# main.net
KiCad netlist of a schematic drawn in EAGLE
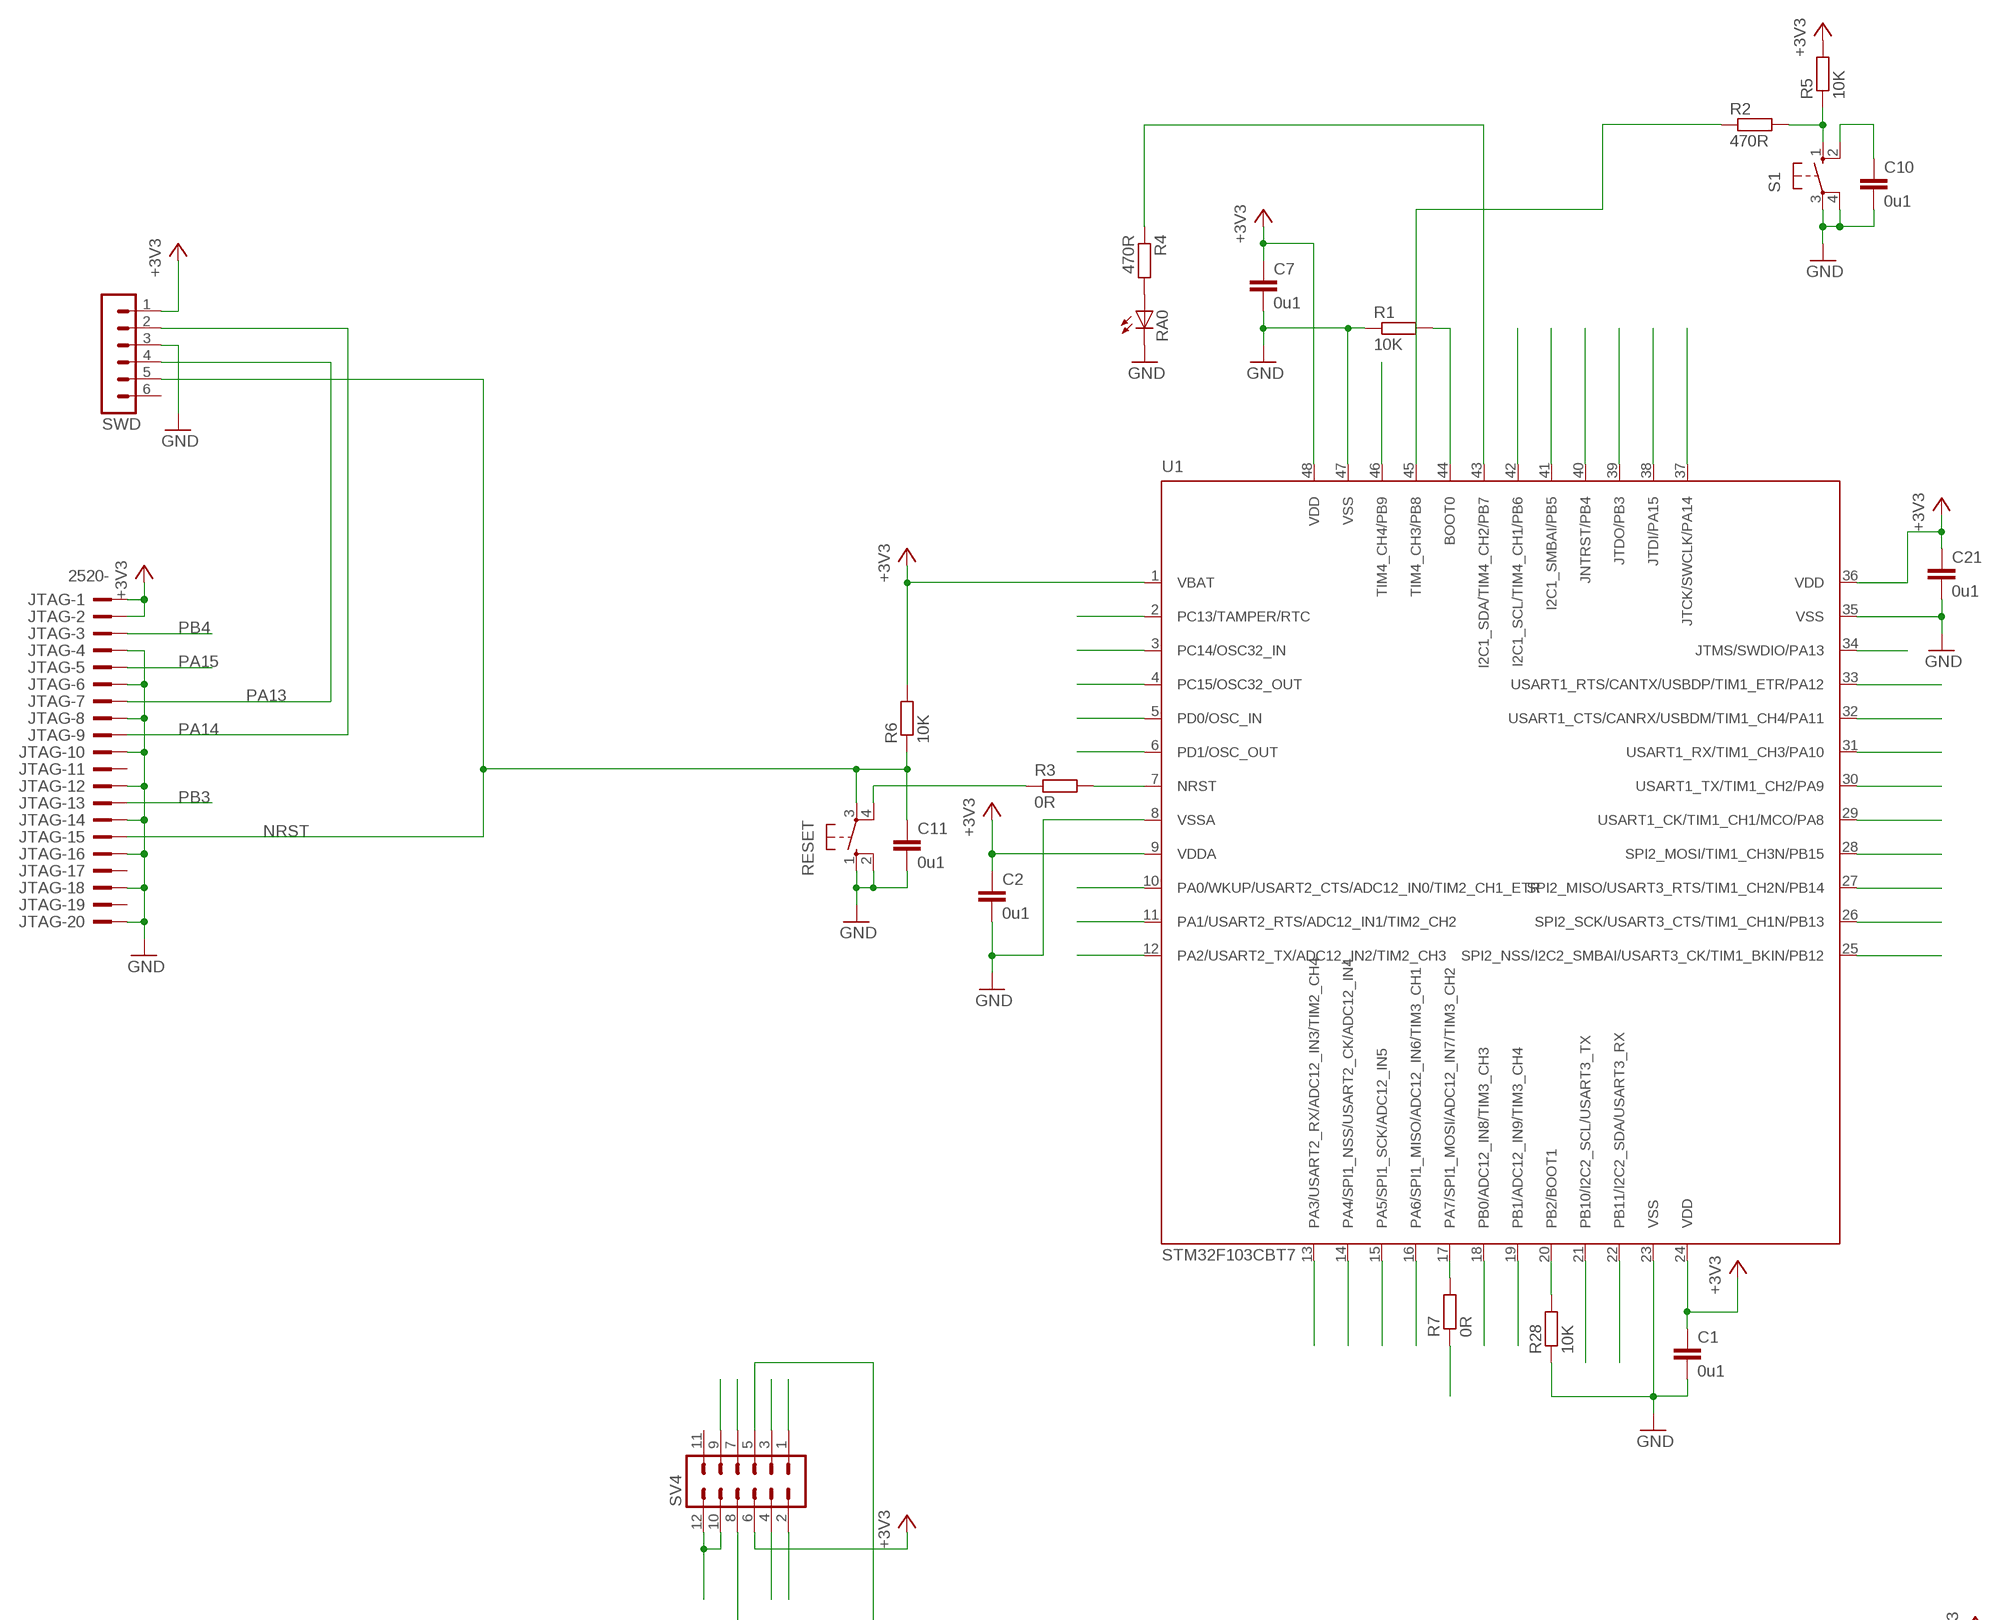
[diagram p0: schematic, sheet 1, part 1 of 2]
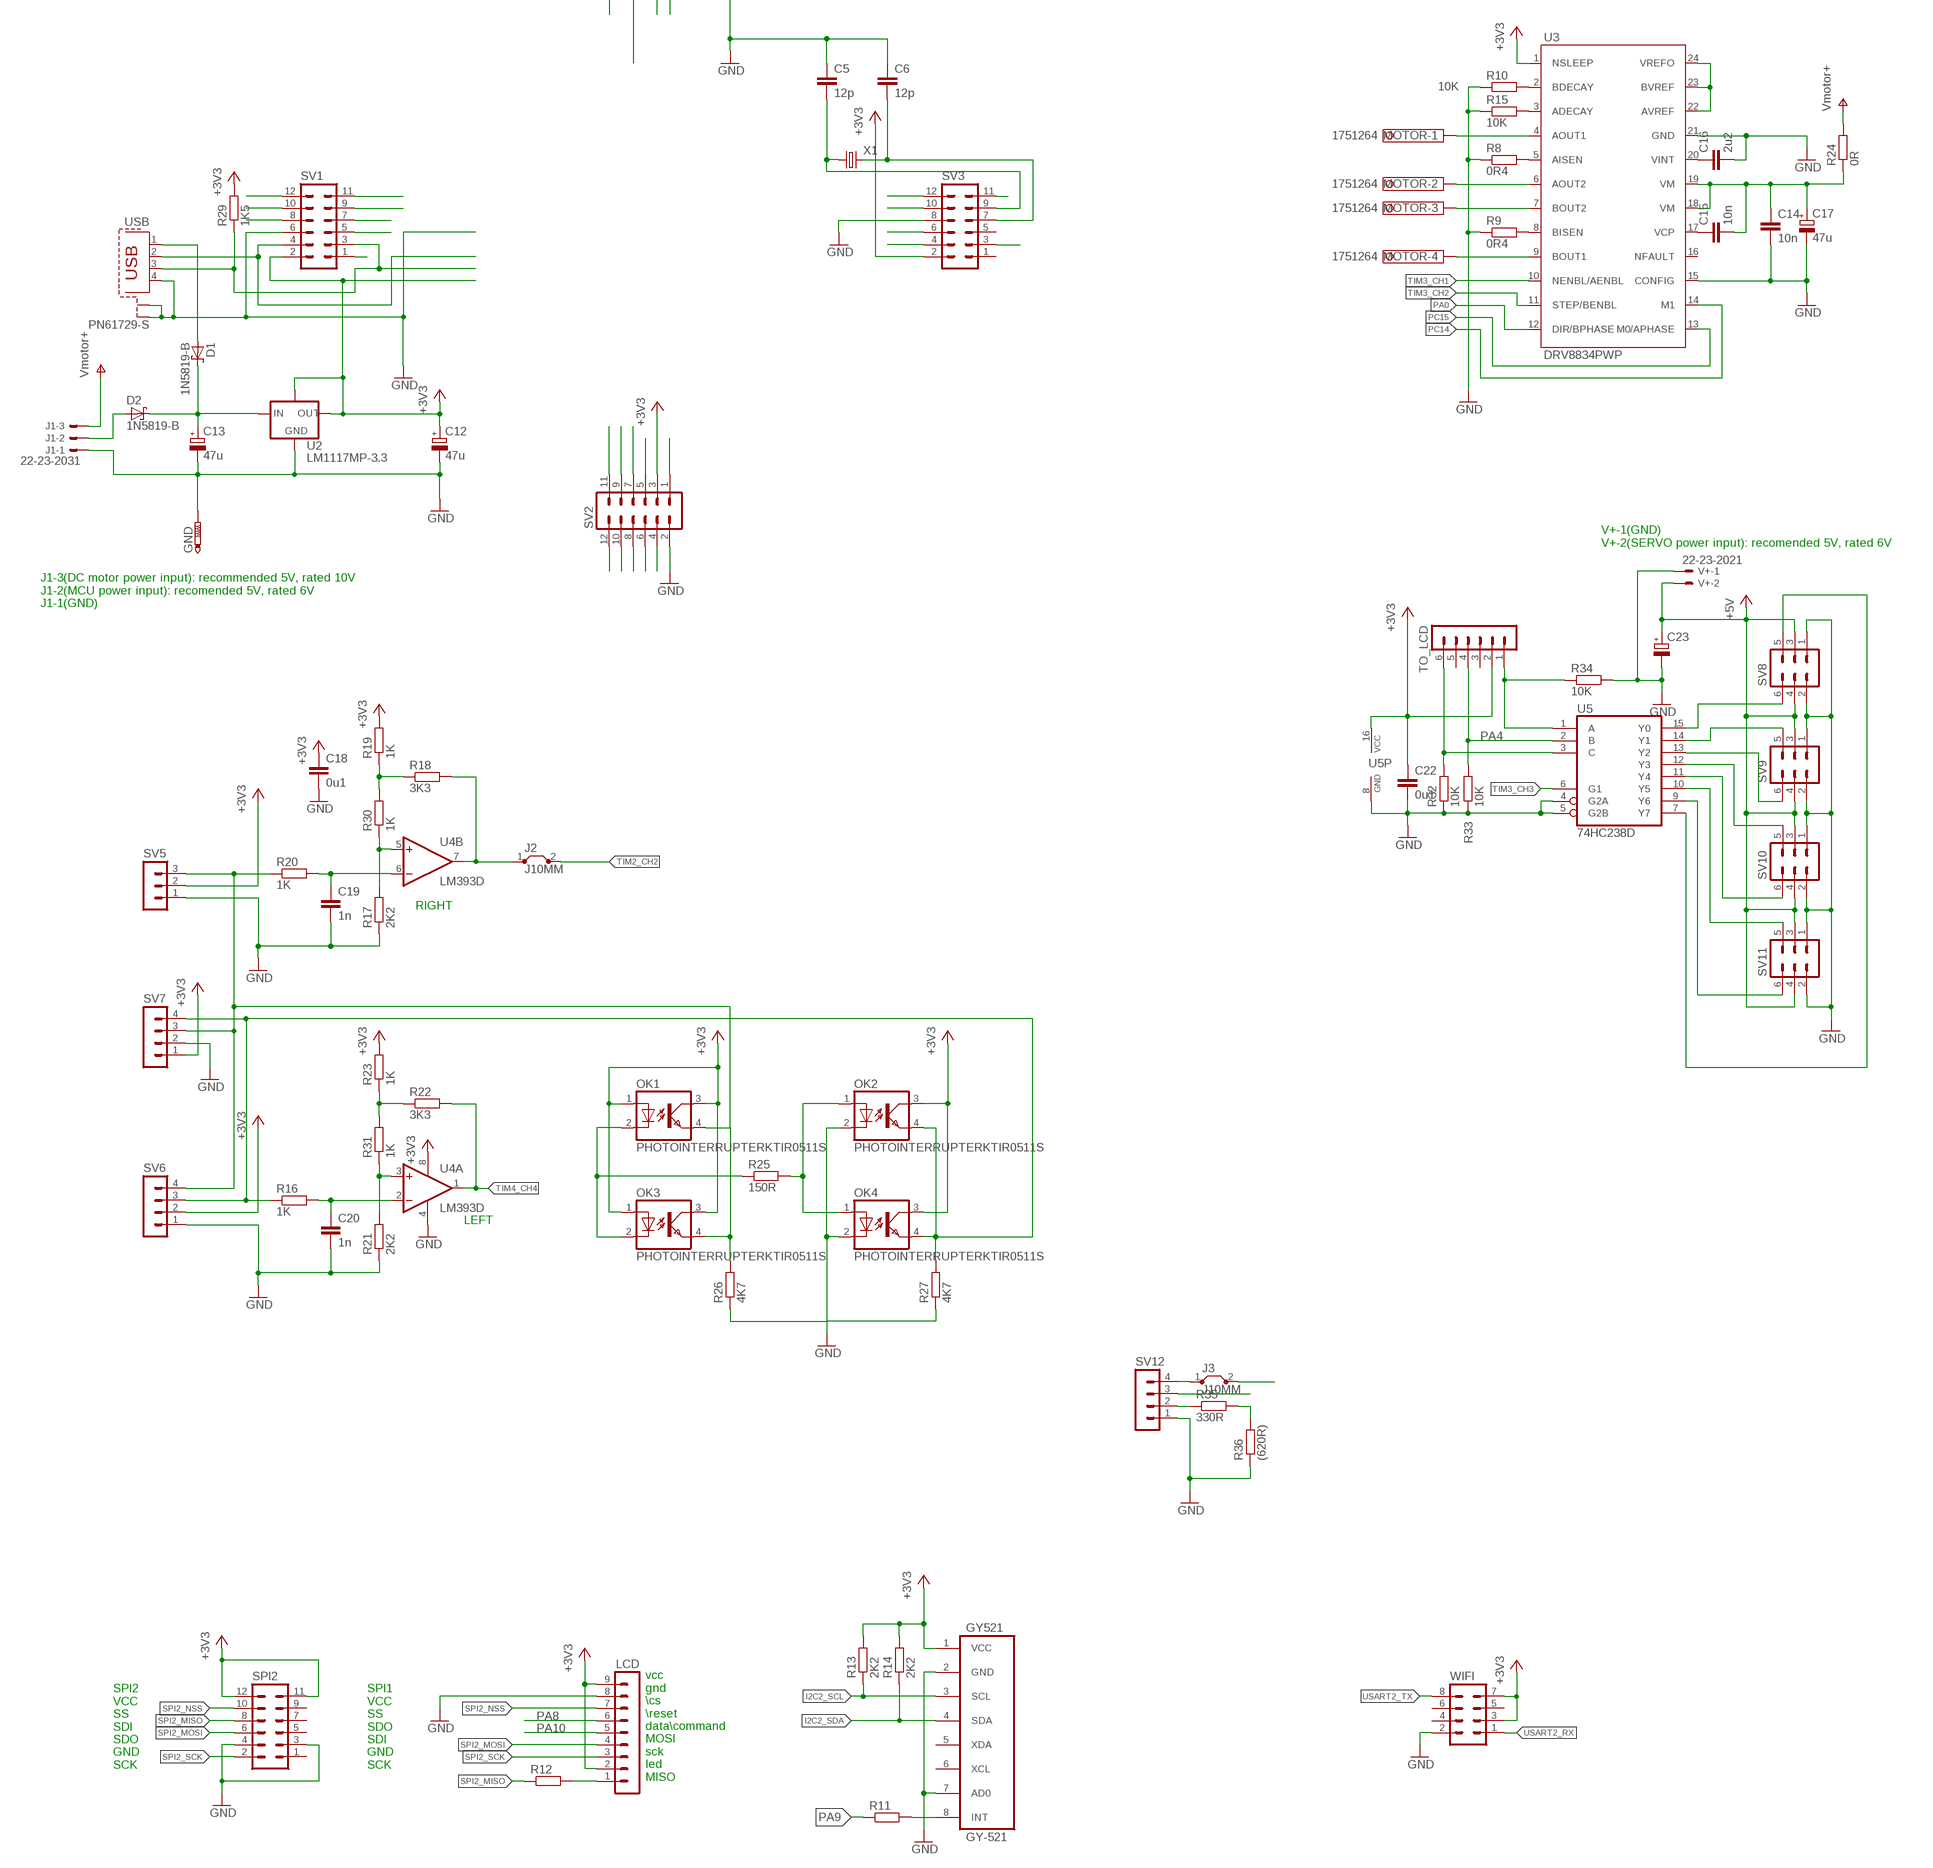
[diagram p1: schematic, sheet 1, part 2 of 2]

(export (version "E")
  (design (tool "Eeschema 10.0.6"))
  (components
    (comp (ref "C1")
      (value "0u1")
      (footprint "eagle-import:C0805")
      (libsource (lib "eagle-import") (part "C-EUC0805"))
    )
    (comp (ref "C2")
      (value "0u1")
      (footprint "eagle-import:C0805")
      (libsource (lib "eagle-import") (part "C-EUC0805"))
    )
    (comp (ref "C5")
      (value "12p")
      (footprint "eagle-import:C0805")
      (libsource (lib "eagle-import") (part "C-EUC0805"))
    )
    (comp (ref "C6")
      (value "12p")
      (footprint "eagle-import:C0805")
      (libsource (lib "eagle-import") (part "C-EUC0805"))
    )
    (comp (ref "C7")
      (value "0u1")
      (footprint "eagle-import:C0805")
      (libsource (lib "eagle-import") (part "C-EUC0805"))
    )
    (comp (ref "C10")
      (value "0u1")
      (footprint "eagle-import:C0805")
      (libsource (lib "eagle-import") (part "C-EUC0805"))
    )
    (comp (ref "C11")
      (value "0u1")
      (footprint "eagle-import:C0805")
      (libsource (lib "eagle-import") (part "C-EUC0805"))
    )
    (comp (ref "C12")
      (value "47u")
      (footprint "eagle-import:E1,8-4")
      (libsource (lib "eagle-import") (part "CPOL-EUE1.8-4"))
    )
    (comp (ref "C13")
      (value "47u")
      (footprint "eagle-import:E1,8-4")
      (libsource (lib "eagle-import") (part "CPOL-EUE1.8-4"))
    )
    (comp (ref "C14")
      (value "10n")
      (footprint "eagle-import:C0805")
      (libsource (lib "eagle-import") (part "C-EUC0805"))
    )
    (comp (ref "C15")
      (value "10n")
      (footprint "eagle-import:C0805")
      (libsource (lib "eagle-import") (part "C-EUC0805"))
    )
    (comp (ref "C16")
      (value "2u2")
      (footprint "eagle-import:C0805")
      (libsource (lib "eagle-import") (part "C-EUC0805"))
    )
    (comp (ref "C17")
      (value "47u")
      (footprint "eagle-import:E1,8-4")
      (libsource (lib "eagle-import") (part "CPOL-EUE1.8-4"))
    )
    (comp (ref "C18")
      (value "0u1")
      (footprint "eagle-import:C0805")
      (libsource (lib "eagle-import") (part "C-EUC0805"))
    )
    (comp (ref "C19")
      (value "1n")
      (footprint "eagle-import:C0805")
      (libsource (lib "eagle-import") (part "C-EUC0805"))
    )
    (comp (ref "C20")
      (value "1n")
      (footprint "eagle-import:C0805")
      (libsource (lib "eagle-import") (part "C-EUC0805"))
    )
    (comp (ref "C21")
      (value "0u1")
      (footprint "eagle-import:C0805")
      (libsource (lib "eagle-import") (part "C-EUC0805"))
    )
    (comp (ref "C22")
      (value "0u1")
      (footprint "eagle-import:C0805")
      (libsource (lib "eagle-import") (part "C-EUC0805"))
    )
    (comp (ref "C23")
      (value "CPOL-EUE2.5-7")
      (footprint "eagle-import:E2,5-7")
      (libsource (lib "eagle-import") (part "CPOL-EUE2.5-7"))
    )
    (comp (ref "D1")
      (value "1N5819-B")
      (footprint "eagle-import:DO41-7.6")
      (libsource (lib "eagle-import") (part "1N5819-B"))
    )
    (comp (ref "D2")
      (value "1N5819-B")
      (footprint "eagle-import:DO41-7.6")
      (libsource (lib "eagle-import") (part "1N5819-B"))
    )
    (comp (ref "GND")
      (value "PTR1PAD1-13")
      (footprint "eagle-import:P1-13")
      (libsource (lib "eagle-import") (part "PTR1PAD1-13"))
    )
    (comp (ref "GY521")
      (value "GY-521")
      (footprint "eagle-import:GY-521")
      (libsource (lib "eagle-import") (part "GY-521"))
    )
    (comp (ref "J1")
      (value "22-23-2031")
      (footprint "eagle-import:22-23-2031")
      (fields (field (name "MF") "MOLEX"))
      (libsource (lib "eagle-import") (part "22-23-2031"))
    )
    (comp (ref "J2")
      (value "J10MM")
      (footprint "eagle-import:10")
      (libsource (lib "eagle-import") (part "J10MM"))
    )
    (comp (ref "J3")
      (value "J10MM")
      (footprint "eagle-import:10")
      (libsource (lib "eagle-import") (part "J10MM"))
    )
    (comp (ref "JTAG")
      (value "2520-")
      (footprint "eagle-import:PAK100_2500-20")
      (libsource (lib "eagle-import") (part "2520-"))
    )
    (comp (ref "LCD")
      (value "MA09-1")
      (footprint "eagle-import:MA09-1")
      (libsource (lib "eagle-import") (part "MA09-1"))
    )
    (comp (ref "MOTOR")
      (value "1751264")
      (footprint "eagle-import:1751264")
      (libsource (lib "eagle-import") (part "1751264"))
    )
    (comp (ref "OK1")
      (value "PHOTOINTERRUPTERKTIR0511S")
      (footprint "eagle-import:KTIR0511S")
      (libsource (lib "eagle-import") (part "PHOTOINTERRUPTERKTIR0511S"))
    )
    (comp (ref "OK2")
      (value "PHOTOINTERRUPTERKTIR0511S")
      (footprint "eagle-import:KTIR0511S")
      (libsource (lib "eagle-import") (part "PHOTOINTERRUPTERKTIR0511S"))
    )
    (comp (ref "OK3")
      (value "PHOTOINTERRUPTERKTIR0511S")
      (footprint "eagle-import:KTIR0511S")
      (libsource (lib "eagle-import") (part "PHOTOINTERRUPTERKTIR0511S"))
    )
    (comp (ref "OK4")
      (value "PHOTOINTERRUPTERKTIR0511S")
      (footprint "eagle-import:KTIR0511S")
      (libsource (lib "eagle-import") (part "PHOTOINTERRUPTERKTIR0511S"))
    )
    (comp (ref "R1")
      (value "10K")
      (footprint "eagle-import:M0805")
      (libsource (lib "eagle-import") (part "R-EU_M0805"))
    )
    (comp (ref "R2")
      (value "470R")
      (footprint "eagle-import:0207_10")
      (libsource (lib "eagle-import") (part "R-EU_0207/10"))
    )
    (comp (ref "R3")
      (value "0R")
      (footprint "eagle-import:0207_10")
      (libsource (lib "eagle-import") (part "R-EU_0207/10"))
    )
    (comp (ref "R4")
      (value "470R")
      (footprint "eagle-import:0207_10")
      (libsource (lib "eagle-import") (part "R-EU_0207/10"))
    )
    (comp (ref "R5")
      (value "10K")
      (footprint "eagle-import:0207_10")
      (libsource (lib "eagle-import") (part "R-EU_0207/10"))
    )
    (comp (ref "R6")
      (value "10K")
      (footprint "eagle-import:M0805")
      (libsource (lib "eagle-import") (part "R-EU_M0805"))
    )
    (comp (ref "R7")
      (value "0R")
      (footprint "eagle-import:0207_10")
      (libsource (lib "eagle-import") (part "R-EU_0207/10"))
    )
    (comp (ref "R8")
      (value "0R4")
      (footprint "eagle-import:R2010")
      (libsource (lib "eagle-import") (part "R-EU_R2010"))
    )
    (comp (ref "R9")
      (value "0R4")
      (footprint "eagle-import:R2010")
      (libsource (lib "eagle-import") (part "R-EU_R2010"))
    )
    (comp (ref "R10")
      (value "10K")
      (footprint "eagle-import:R0805")
      (libsource (lib "eagle-import") (part "R-EU_R0805"))
    )
    (comp (ref "R11")
      (value "R-EU_0207/10")
      (footprint "eagle-import:0207_10")
      (libsource (lib "eagle-import") (part "R-EU_0207/10"))
    )
    (comp (ref "R12")
      (value "R-EU_0207/10")
      (footprint "eagle-import:0207_10")
      (libsource (lib "eagle-import") (part "R-EU_0207/10"))
    )
    (comp (ref "R13")
      (value "2K2")
      (footprint "eagle-import:M0805")
      (libsource (lib "eagle-import") (part "R-EU_M0805"))
    )
    (comp (ref "R14")
      (value "2K2")
      (footprint "eagle-import:M0805")
      (libsource (lib "eagle-import") (part "R-EU_M0805"))
    )
    (comp (ref "R15")
      (value "10K")
      (footprint "eagle-import:R0805")
      (libsource (lib "eagle-import") (part "R-EU_R0805"))
    )
    (comp (ref "R16")
      (value "1K")
      (footprint "eagle-import:0207_10")
      (libsource (lib "eagle-import") (part "R-EU_0207/10"))
    )
    (comp (ref "R17")
      (value "2K2")
      (footprint "eagle-import:M0805")
      (libsource (lib "eagle-import") (part "R-EU_M0805"))
    )
    (comp (ref "R18")
      (value "3K3")
      (footprint "eagle-import:M0805")
      (libsource (lib "eagle-import") (part "R-EU_M0805"))
    )
    (comp (ref "R19")
      (value "1K")
      (footprint "eagle-import:M0805")
      (libsource (lib "eagle-import") (part "R-EU_M0805"))
    )
    (comp (ref "R20")
      (value "1K")
      (footprint "eagle-import:0207_10")
      (libsource (lib "eagle-import") (part "R-EU_0207/10"))
    )
    (comp (ref "R21")
      (value "2K2")
      (footprint "eagle-import:M0805")
      (libsource (lib "eagle-import") (part "R-EU_M0805"))
    )
    (comp (ref "R22")
      (value "3K3")
      (footprint "eagle-import:M0805")
      (libsource (lib "eagle-import") (part "R-EU_M0805"))
    )
    (comp (ref "R23")
      (value "1K")
      (footprint "eagle-import:M0805")
      (libsource (lib "eagle-import") (part "R-EU_M0805"))
    )
    (comp (ref "R24")
      (value "0R")
      (footprint "eagle-import:0207_10")
      (libsource (lib "eagle-import") (part "R-EU_0207/10"))
    )
    (comp (ref "R25")
      (value "150R")
      (footprint "eagle-import:0207_10")
      (libsource (lib "eagle-import") (part "R-EU_0207/10"))
    )
    (comp (ref "R26")
      (value "4K7")
      (footprint "eagle-import:M0805")
      (libsource (lib "eagle-import") (part "R-EU_M0805"))
    )
    (comp (ref "R27")
      (value "4K7")
      (footprint "eagle-import:M0805")
      (libsource (lib "eagle-import") (part "R-EU_M0805"))
    )
    (comp (ref "R28")
      (value "10K")
      (footprint "eagle-import:M0805")
      (libsource (lib "eagle-import") (part "R-EU_M0805"))
    )
    (comp (ref "R29")
      (value "1K5")
      (footprint "eagle-import:M0805")
      (libsource (lib "eagle-import") (part "R-EU_M0805"))
    )
    (comp (ref "R30")
      (value "1K")
      (footprint "eagle-import:M0805")
      (libsource (lib "eagle-import") (part "R-EU_M0805"))
    )
    (comp (ref "R31")
      (value "1K")
      (footprint "eagle-import:M0805")
      (libsource (lib "eagle-import") (part "R-EU_M0805"))
    )
    (comp (ref "R32")
      (value "10K")
      (footprint "eagle-import:M0805")
      (libsource (lib "eagle-import") (part "R-EU_M0805"))
    )
    (comp (ref "R33")
      (value "10K")
      (footprint "eagle-import:M0805")
      (libsource (lib "eagle-import") (part "R-EU_M0805"))
    )
    (comp (ref "R34")
      (value "10K")
      (footprint "eagle-import:M0805")
      (libsource (lib "eagle-import") (part "R-EU_M0805"))
    )
    (comp (ref "R35")
      (value "330R")
      (footprint "eagle-import:M0805")
      (libsource (lib "eagle-import") (part "R-EU_M0805"))
    )
    (comp (ref "R36")
      (value "(620R)")
      (footprint "eagle-import:M0805")
      (libsource (lib "eagle-import") (part "R-EU_M0805"))
    )
    (comp (ref "RA0")
      (value "LED3MM")
      (footprint "eagle-import:LED3MM")
      (libsource (lib "eagle-import") (part "LED3MM"))
    )
    (comp (ref "RESET")
      (value "10-XX")
      (footprint "eagle-import:B3F-10XX")
      (fields (field (name "MPN") "B3F-1000"))
      (libsource (lib "eagle-import") (part "10-XX"))
    )
    (comp (ref "S1")
      (value "10-XX")
      (footprint "eagle-import:B3F-10XX")
      (fields (field (name "MPN") "B3F-1000"))
      (libsource (lib "eagle-import") (part "10-XX"))
    )
    (comp (ref "SPI2")
      (value "MA06-2")
      (footprint "eagle-import:MA06-2")
      (libsource (lib "eagle-import") (part "MA06-2"))
    )
    (comp (ref "SV1")
      (value "MA06-2")
      (footprint "eagle-import:MA06-2")
      (libsource (lib "eagle-import") (part "MA06-2"))
    )
    (comp (ref "SV2")
      (value "MA06-2")
      (footprint "eagle-import:MA06-2")
      (libsource (lib "eagle-import") (part "MA06-2"))
    )
    (comp (ref "SV3")
      (value "MA06-2")
      (footprint "eagle-import:MA06-2")
      (libsource (lib "eagle-import") (part "MA06-2"))
    )
    (comp (ref "SV4")
      (value "MA06-2")
      (footprint "eagle-import:MA06-2")
      (libsource (lib "eagle-import") (part "MA06-2"))
    )
    (comp (ref "SV5")
      (value "MA03-1")
      (footprint "eagle-import:MA03-1")
      (libsource (lib "eagle-import") (part "MA03-1"))
    )
    (comp (ref "SV6")
      (value "MA04-1")
      (footprint "eagle-import:MA04-1")
      (libsource (lib "eagle-import") (part "MA04-1"))
    )
    (comp (ref "SV7")
      (value "MA04-1")
      (footprint "eagle-import:MA04-1")
      (libsource (lib "eagle-import") (part "MA04-1"))
    )
    (comp (ref "SV8")
      (value "MA03-2")
      (footprint "eagle-import:MA03-2")
      (libsource (lib "eagle-import") (part "MA03-2"))
    )
    (comp (ref "SV9")
      (value "MA03-2")
      (footprint "eagle-import:MA03-2")
      (libsource (lib "eagle-import") (part "MA03-2"))
    )
    (comp (ref "SV10")
      (value "MA03-2")
      (footprint "eagle-import:MA03-2")
      (libsource (lib "eagle-import") (part "MA03-2"))
    )
    (comp (ref "SV11")
      (value "MA03-2")
      (footprint "eagle-import:MA03-2")
      (libsource (lib "eagle-import") (part "MA03-2"))
    )
    (comp (ref "SV12")
      (value "MA04-1")
      (footprint "eagle-import:MA04-1")
      (libsource (lib "eagle-import") (part "MA04-1"))
    )
    (comp (ref "SWD")
      (value "MA06-1")
      (footprint "eagle-import:MA06-1")
      (libsource (lib "eagle-import") (part "MA06-1"))
    )
    (comp (ref "TO_LCD")
      (value "MA06-1")
      (footprint "eagle-import:MA06-1")
      (libsource (lib "eagle-import") (part "MA06-1"))
    )
    (comp (ref "U1")
      (value "STM32F103CBT7")
      (footprint "eagle-import:LQFP48-7X7")
      (libsource (lib "eagle-import") (part "STM32F103CBT7"))
    )
    (comp (ref "U2")
      (value "LM1117MP-3.3")
      (footprint "eagle-import:SOT230P700X180-4N")
      (libsource (lib "eagle-import") (part "LM1117"))
    )
    (comp (ref "U3")
      (value "DRV8834PWP")
      (footprint "eagle-import:PWP-TSSOP24")
      (libsource (lib "eagle-import") (part "DRV8834PWP"))
    )
    (comp (ref "U4")
      (value "LM393D")
      (footprint "eagle-import:SO08")
      (libsource (lib "eagle-import") (part "LM393D"))
    )
    (comp (ref "U5")
      (value "74HC238D")
      (footprint "eagle-import:SO16")
      (libsource (lib "eagle-import") (part "74238DHC"))
    )
    (comp (ref "USB")
      (value "PN61729-S")
      (footprint "eagle-import:PN61729-S")
      (libsource (lib "eagle-import") (part "PN61729-S"))
    )
    (comp (ref "V+")
      (value "22-23-2021")
      (footprint "eagle-import:22-23-2021")
      (fields (field (name "MF") "MOLEX"))
      (libsource (lib "eagle-import") (part "22-23-2021"))
    )
    (comp (ref "WIFI")
      (value "MA04-2")
      (footprint "eagle-import:MA04-2")
      (libsource (lib "eagle-import") (part "MA04-2"))
    )
    (comp (ref "X1")
      (value "CRYSTALHC49S")
      (footprint "eagle-import:HC49_S")
      (libsource (lib "eagle-import") (part "CRYSTALHC49S"))
    )
  )
  (nets
    (net (code "1") (name "+3V3") (class "Default")
      (node (ref "C1") (pin "1") (pinfunction "1_1") (pintype "passive"))
      (node (ref "C12") (pin "+") (pinfunction "+_+") (pintype "passive"))
      (node (ref "C18") (pin "1") (pinfunction "1_1") (pintype "passive"))
      (node (ref "C2") (pin "1") (pinfunction "1_1") (pintype "passive"))
      (node (ref "C21") (pin "1") (pinfunction "1_1") (pintype "passive"))
      (node (ref "C22") (pin "1") (pinfunction "1_1") (pintype "passive"))
      (node (ref "C7") (pin "1") (pinfunction "1_1") (pintype "passive"))
      (node (ref "GY521") (pin "1") (pinfunction "VCC_1") (pintype "power_in"))
      (node (ref "JTAG") (pin "1") (pinfunction "KL_1") (pintype "passive"))
      (node (ref "JTAG") (pin "2") (pinfunction "KL_2") (pintype "passive"))
      (node (ref "LCD") (pin "2") (pinfunction "2_2") (pintype "passive"))
      (node (ref "LCD") (pin "9") (pinfunction "9_9") (pintype "passive"))
      (node (ref "OK1") (pin "1") (pinfunction "A_1") (pintype "passive"))
      (node (ref "OK1") (pin "3") (pinfunction "COL_3") (pintype "passive"))
      (node (ref "OK2") (pin "3") (pinfunction "COL_3") (pintype "passive"))
      (node (ref "OK3") (pin "1") (pinfunction "A_1") (pintype "passive"))
      (node (ref "OK3") (pin "3") (pinfunction "COL_3") (pintype "passive"))
      (node (ref "OK4") (pin "3") (pinfunction "COL_3") (pintype "passive"))
      (node (ref "R13") (pin "2") (pinfunction "2_2") (pintype "passive"))
      (node (ref "R14") (pin "2") (pinfunction "2_2") (pintype "passive"))
      (node (ref "R19") (pin "2") (pinfunction "2_2") (pintype "passive"))
      (node (ref "R23") (pin "2") (pinfunction "2_2") (pintype "passive"))
      (node (ref "R29") (pin "2") (pinfunction "2_2") (pintype "passive"))
      (node (ref "R5") (pin "2") (pinfunction "2_2") (pintype "passive"))
      (node (ref "R6") (pin "2") (pinfunction "2_2") (pintype "passive"))
      (node (ref "SPI2") (pin "11") (pinfunction "11_11") (pintype "passive"))
      (node (ref "SPI2") (pin "12") (pinfunction "12_12") (pintype "passive"))
      (node (ref "SV1") (pin "2") (pinfunction "2_2") (pintype "passive"))
      (node (ref "SV2") (pin "3") (pinfunction "3_3") (pintype "passive"))
      (node (ref "SV3") (pin "2") (pinfunction "2_2") (pintype "passive"))
      (node (ref "SV4") (pin "6") (pinfunction "6_6") (pintype "passive"))
      (node (ref "SV5") (pin "2") (pinfunction "2_2") (pintype "passive"))
      (node (ref "SV6") (pin "2") (pinfunction "2_2") (pintype "passive"))
      (node (ref "SV7") (pin "1") (pinfunction "1_1") (pintype "passive"))
      (node (ref "SWD") (pin "1") (pinfunction "1_1") (pintype "passive"))
      (node (ref "TO_LCD") (pin "2") (pinfunction "2_2") (pintype "passive"))
      (node (ref "U1") (pin "1") (pinfunction "VBAT_1") (pintype "input"))
      (node (ref "U1") (pin "24") (pinfunction "VDD_24") (pintype "power_in"))
      (node (ref "U1") (pin "36") (pinfunction "VDD_36") (pintype "power_in"))
      (node (ref "U1") (pin "48") (pinfunction "VDD_48") (pintype "power_in"))
      (node (ref "U1") (pin "9") (pinfunction "VDDA_9") (pintype "power_in"))
      (node (ref "U2") (pin "2") (pinfunction "OUT_2") (pintype "passive"))
      (node (ref "U2") (pin "4") (pinfunction "TAB_4") (pintype "passive"))
      (node (ref "U3") (pin "1") (pinfunction "NSLEEP_1") (pintype "passive"))
      (node (ref "U4") (pin "8") (pinfunction "V+_8") (pintype "power_in"))
      (node (ref "U5") (pin "16") (pinfunction "VCC_16") (pintype "power_in"))
      (node (ref "WIFI") (pin "3") (pinfunction "3_3") (pintype "passive"))
      (node (ref "WIFI") (pin "7") (pinfunction "7_7") (pintype "passive"))
    )
    (net (code "2") (name "+5V") (class "Default")
      (node (ref "C23") (pin "+") (pinfunction "+_+") (pintype "passive"))
      (node (ref "SV10") (pin "3") (pinfunction "3_3") (pintype "passive"))
      (node (ref "SV10") (pin "4") (pinfunction "4_4") (pintype "passive"))
      (node (ref "SV11") (pin "3") (pinfunction "3_3") (pintype "passive"))
      (node (ref "SV11") (pin "4") (pinfunction "4_4") (pintype "passive"))
      (node (ref "SV8") (pin "3") (pinfunction "3_3") (pintype "passive"))
      (node (ref "SV8") (pin "4") (pinfunction "4_4") (pintype "passive"))
      (node (ref "SV9") (pin "3") (pinfunction "3_3") (pintype "passive"))
      (node (ref "SV9") (pin "4") (pinfunction "4_4") (pintype "passive"))
      (node (ref "V+") (pin "2") (pinfunction "S_2") (pintype "passive"))
    )
    (net (code "3") (name "/BOOT0") (class "Default")
      (node (ref "R1") (pin "2") (pinfunction "2_2") (pintype "passive"))
      (node (ref "SV2") (pin "5") (pinfunction "5_5") (pintype "passive"))
      (node (ref "U1") (pin "44") (pinfunction "BOOT0_44") (pintype "input"))
    )
    (net (code "4") (name "/BOOT1") (class "Default")
      (node (ref "R28") (pin "2") (pinfunction "2_2") (pintype "passive"))
      (node (ref "SV4") (pin "8") (pinfunction "8_8") (pintype "passive"))
      (node (ref "U1") (pin "20") (pinfunction "PB2/BOOT1_20") (pintype "bidirectional"))
    )
    (net (code "5") (name "/N$13") (class "Default")
      (node (ref "D2") (pin "A") (pinfunction "A_A") (pintype "passive"))
      (node (ref "J1") (pin "2") (pinfunction "S_2") (pintype "passive"))
      (node (ref "J3") (pin "2") (pinfunction "2_2") (pintype "passive"))
    )
    (net (code "6") (name "/NRST") (class "Default")
      (node (ref "C11") (pin "1") (pinfunction "1_1") (pintype "passive"))
      (node (ref "JTAG") (pin "15") (pinfunction "KL_15") (pintype "passive"))
      (node (ref "R6") (pin "1") (pinfunction "1_1") (pintype "passive"))
      (node (ref "RESET") (pin "3") (pinfunction "P_3") (pintype "passive"))
      (node (ref "SWD") (pin "5") (pinfunction "5_5") (pintype "passive"))
    )
    (net (code "7") (name "/PA4") (class "Default")
      (node (ref "R33") (pin "2") (pinfunction "2_2") (pintype "passive"))
      (node (ref "SV4") (pin "1") (pinfunction "1_1") (pintype "passive"))
      (node (ref "TO_LCD") (pin "4") (pinfunction "4_4") (pintype "passive"))
      (node (ref "U1") (pin "14") (pinfunction "PA4/SPI1_NSS/USART2_CK/ADC12_IN4_14") (pintype "bidirectional"))
      (node (ref "U5") (pin "2") (pinfunction "B_2") (pintype "input"))
    )
    (net (code "8") (name "/PA5") (class "Default")
      (node (ref "SV4") (pin "2") (pinfunction "2_2") (pintype "passive"))
      (node (ref "U1") (pin "15") (pinfunction "PA5/SPI1_SCK/ADC12_IN5_15") (pintype "bidirectional"))
    )
    (net (code "9") (name "/PA8") (class "Default")
      (node (ref "LCD") (pin "6") (pinfunction "6_6") (pintype "passive"))
      (node (ref "SV1") (pin "7") (pinfunction "7_7") (pintype "passive"))
      (node (ref "U1") (pin "29") (pinfunction "USART1_CK/TIM1_CH1/MCO/PA8_29") (pintype "bidirectional"))
    )
    (net (code "10") (name "/PA10") (class "Default")
      (node (ref "LCD") (pin "5") (pinfunction "5_5") (pintype "passive"))
      (node (ref "SV1") (pin "5") (pinfunction "5_5") (pintype "passive"))
      (node (ref "U1") (pin "31") (pinfunction "USART1_RX/TIM1_CH3/PA10_31") (pintype "bidirectional"))
    )
    (net (code "11") (name "/PA13") (class "Default")
      (node (ref "JTAG") (pin "7") (pinfunction "KL_7") (pintype "passive"))
      (node (ref "SV1") (pin "1") (pinfunction "1_1") (pintype "passive"))
      (node (ref "SWD") (pin "4") (pinfunction "4_4") (pintype "passive"))
      (node (ref "U1") (pin "34") (pinfunction "JTMS/SWDIO/PA13_34") (pintype "bidirectional"))
    )
    (net (code "12") (name "/PA14") (class "Default")
      (node (ref "JTAG") (pin "9") (pinfunction "KL_9") (pintype "passive"))
      (node (ref "SV2") (pin "12") (pinfunction "12_12") (pintype "passive"))
      (node (ref "SWD") (pin "2") (pinfunction "2_2") (pintype "passive"))
      (node (ref "U1") (pin "37") (pinfunction "JTCK/SWCLK/PA14_37") (pintype "bidirectional"))
    )
    (net (code "13") (name "/PA15") (class "Default")
      (node (ref "JTAG") (pin "5") (pinfunction "KL_5") (pintype "passive"))
      (node (ref "SV2") (pin "11") (pinfunction "11_11") (pintype "passive"))
      (node (ref "U1") (pin "38") (pinfunction "JTDI/PA15_38") (pintype "bidirectional"))
    )
    (net (code "14") (name "/PB1") (class "Default")
      (node (ref "SV4") (pin "7") (pinfunction "7_7") (pintype "passive"))
      (node (ref "U1") (pin "19") (pinfunction "PB1/ADC12_IN9/TIM3_CH4_19") (pintype "bidirectional"))
    )
    (net (code "15") (name "/PB3") (class "Default")
      (node (ref "JTAG") (pin "13") (pinfunction "KL_13") (pintype "passive"))
      (node (ref "SV2") (pin "10") (pinfunction "10_10") (pintype "passive"))
      (node (ref "U1") (pin "39") (pinfunction "JTDO/PB3_39") (pintype "bidirectional"))
    )
    (net (code "16") (name "/PB4") (class "Default")
      (node (ref "JTAG") (pin "3") (pinfunction "KL_3") (pintype "passive"))
      (node (ref "R35") (pin "2") (pinfunction "2_2") (pintype "passive"))
      (node (ref "R36") (pin "2") (pinfunction "2_2") (pintype "passive"))
      (node (ref "SV2") (pin "9") (pinfunction "9_9") (pintype "passive"))
      (node (ref "U1") (pin "40") (pinfunction "JNTRST/PB4_40") (pintype "bidirectional"))
    )
    (net (code "17") (name "/PB5") (class "Default")
      (node (ref "SV12") (pin "3") (pinfunction "3_3") (pintype "passive"))
      (node (ref "SV2") (pin "8") (pinfunction "8_8") (pintype "passive"))
      (node (ref "U1") (pin "41") (pinfunction "I2C1_SMBAI/PB5_41") (pintype "bidirectional"))
    )
    (net (code "18") (name "/PB6") (class "Default")
      (node (ref "SV2") (pin "7") (pinfunction "7_7") (pintype "passive"))
      (node (ref "U1") (pin "42") (pinfunction "I2C1_SCL/TIM4_CH1/PB6_42") (pintype "bidirectional"))
    )
    (net (code "19") (name "/PB7") (class "Default")
      (node (ref "R4") (pin "1") (pinfunction "1_1") (pintype "passive"))
      (node (ref "SV2") (pin "6") (pinfunction "6_6") (pintype "passive"))
      (node (ref "U1") (pin "43") (pinfunction "I2C1_SDA/TIM4_CH2/PB7_43") (pintype "bidirectional"))
    )
    (net (code "20") (name "/PB8") (class "Default")
      (node (ref "R2") (pin "1") (pinfunction "1_1") (pintype "passive"))
      (node (ref "SV2") (pin "4") (pinfunction "4_4") (pintype "passive"))
      (node (ref "U1") (pin "45") (pinfunction "TIM4_CH3/PB8_45") (pintype "bidirectional"))
    )
    (net (code "21") (name "/PC13") (class "Default")
      (node (ref "SV3") (pin "4") (pinfunction "4_4") (pintype "passive"))
      (node (ref "U1") (pin "2") (pinfunction "PC13/TAMPER/RTC_2") (pintype "bidirectional"))
    )
    (net (code "22") (name "/PD0") (class "Default")
      (node (ref "C6") (pin "2") (pinfunction "2_2") (pintype "passive"))
      (node (ref "SV3") (pin "7") (pinfunction "7_7") (pintype "passive"))
      (node (ref "U1") (pin "5") (pinfunction "PD0/OSC_IN_5") (pintype "bidirectional"))
      (node (ref "X1") (pin "2") (pinfunction "2_2") (pintype "passive"))
    )
    (net (code "23") (name "/PD1") (class "Default")
      (node (ref "C5") (pin "2") (pinfunction "2_2") (pintype "passive"))
      (node (ref "SV3") (pin "9") (pinfunction "9_9") (pintype "passive"))
      (node (ref "U1") (pin "6") (pinfunction "PD1/OSC_OUT_6") (pintype "bidirectional"))
      (node (ref "X1") (pin "1") (pinfunction "1_1") (pintype "passive"))
    )
    (net (code "24") (name "/USBDM") (class "Default")
      (node (ref "SV1") (pin "4") (pinfunction "4_4") (pintype "passive"))
      (node (ref "U1") (pin "32") (pinfunction "USART1_CTS/CANRX/USBDM/TIM1_CH4/PA11_32") (pintype "bidirectional"))
      (node (ref "USB") (pin "2") (pinfunction "2_2") (pintype "passive"))
    )
    (net (code "25") (name "/USBDP") (class "Default")
      (node (ref "R29") (pin "1") (pinfunction "1_1") (pintype "passive"))
      (node (ref "SV1") (pin "3") (pinfunction "3_3") (pintype "passive"))
      (node (ref "U1") (pin "33") (pinfunction "USART1_RTS/CANTX/USBDP/TIM1_ETR/PA12_33") (pintype "bidirectional"))
      (node (ref "USB") (pin "3") (pinfunction "3_3") (pintype "passive"))
    )
    (net (code "26") (name "GND") (class "Default")
      (node (ref "C1") (pin "2") (pinfunction "2_2") (pintype "passive"))
      (node (ref "C10") (pin "2") (pinfunction "2_2") (pintype "passive"))
      (node (ref "C11") (pin "2") (pinfunction "2_2") (pintype "passive"))
      (node (ref "C12") (pin "-") (pinfunction "-_-") (pintype "passive"))
      (node (ref "C13") (pin "-") (pinfunction "-_-") (pintype "passive"))
      (node (ref "C14") (pin "2") (pinfunction "2_2") (pintype "passive"))
      (node (ref "C16") (pin "2") (pinfunction "2_2") (pintype "passive"))
      (node (ref "C17") (pin "-") (pinfunction "-_-") (pintype "passive"))
      (node (ref "C18") (pin "2") (pinfunction "2_2") (pintype "passive"))
      (node (ref "C19") (pin "2") (pinfunction "2_2") (pintype "passive"))
      (node (ref "C2") (pin "2") (pinfunction "2_2") (pintype "passive"))
      (node (ref "C20") (pin "2") (pinfunction "2_2") (pintype "passive"))
      (node (ref "C21") (pin "2") (pinfunction "2_2") (pintype "passive"))
      (node (ref "C22") (pin "2") (pinfunction "2_2") (pintype "passive"))
      (node (ref "C23") (pin "-") (pinfunction "-_-") (pintype "passive"))
      (node (ref "C5") (pin "1") (pinfunction "1_1") (pintype "passive"))
      (node (ref "C6") (pin "1") (pinfunction "1_1") (pintype "passive"))
      (node (ref "C7") (pin "2") (pinfunction "2_2") (pintype "passive"))
      (node (ref "GND") (pin "TP") (pinfunction "TP_TP") (pintype "input"))
      (node (ref "GY521") (pin "2") (pinfunction "GND_2") (pintype "power_in"))
      (node (ref "GY521") (pin "7") (pinfunction "AD0_7") (pintype "input"))
      (node (ref "J1") (pin "1") (pinfunction "S_1") (pintype "passive"))
      (node (ref "JTAG") (pin "10") (pinfunction "KL_10") (pintype "passive"))
      (node (ref "JTAG") (pin "12") (pinfunction "KL_12") (pintype "passive"))
      (node (ref "JTAG") (pin "14") (pinfunction "KL_14") (pintype "passive"))
      (node (ref "JTAG") (pin "16") (pinfunction "KL_16") (pintype "passive"))
      (node (ref "JTAG") (pin "18") (pinfunction "KL_18") (pintype "passive"))
      (node (ref "JTAG") (pin "20") (pinfunction "KL_20") (pintype "passive"))
      (node (ref "JTAG") (pin "4") (pinfunction "KL_4") (pintype "passive"))
      (node (ref "JTAG") (pin "6") (pinfunction "KL_6") (pintype "passive"))
      (node (ref "JTAG") (pin "8") (pinfunction "KL_8") (pintype "passive"))
      (node (ref "LCD") (pin "8") (pinfunction "8_8") (pintype "passive"))
      (node (ref "OK2") (pin "2") (pinfunction "C_2") (pintype "passive"))
      (node (ref "OK4") (pin "2") (pinfunction "C_2") (pintype "passive"))
      (node (ref "R1") (pin "1") (pinfunction "1_1") (pintype "passive"))
      (node (ref "R10") (pin "1") (pinfunction "1_1") (pintype "passive"))
      (node (ref "R15") (pin "1") (pinfunction "1_1") (pintype "passive"))
      (node (ref "R17") (pin "1") (pinfunction "1_1") (pintype "passive"))
      (node (ref "R21") (pin "1") (pinfunction "1_1") (pintype "passive"))
      (node (ref "R26") (pin "1") (pinfunction "1_1") (pintype "passive"))
      (node (ref "R27") (pin "1") (pinfunction "1_1") (pintype "passive"))
      (node (ref "R28") (pin "1") (pinfunction "1_1") (pintype "passive"))
      (node (ref "R32") (pin "1") (pinfunction "1_1") (pintype "passive"))
      (node (ref "R33") (pin "1") (pinfunction "1_1") (pintype "passive"))
      (node (ref "R34") (pin "2") (pinfunction "2_2") (pintype "passive"))
      (node (ref "R36") (pin "1") (pinfunction "1_1") (pintype "passive"))
      (node (ref "R8") (pin "1") (pinfunction "1_1") (pintype "passive"))
      (node (ref "R9") (pin "1") (pinfunction "1_1") (pintype "passive"))
      (node (ref "RA0") (pin "K") (pinfunction "C_K") (pintype "passive"))
      (node (ref "RESET") (pin "1") (pinfunction "S_1") (pintype "passive"))
      (node (ref "RESET") (pin "2") (pinfunction "S1_2") (pintype "passive"))
      (node (ref "S1") (pin "3") (pinfunction "P_3") (pintype "passive"))
      (node (ref "S1") (pin "4") (pinfunction "P1_4") (pintype "passive"))
      (node (ref "SPI2") (pin "3") (pinfunction "3_3") (pintype "passive"))
      (node (ref "SPI2") (pin "4") (pinfunction "4_4") (pintype "passive"))
      (node (ref "SV1") (pin "6") (pinfunction "6_6") (pintype "passive"))
      (node (ref "SV10") (pin "1") (pinfunction "1_1") (pintype "passive"))
      (node (ref "SV10") (pin "2") (pinfunction "2_2") (pintype "passive"))
      (node (ref "SV11") (pin "1") (pinfunction "1_1") (pintype "passive"))
      (node (ref "SV11") (pin "2") (pinfunction "2_2") (pintype "passive"))
      (node (ref "SV12") (pin "1") (pinfunction "1_1") (pintype "passive"))
      (node (ref "SV2") (pin "2") (pinfunction "2_2") (pintype "passive"))
      (node (ref "SV3") (pin "8") (pinfunction "8_8") (pintype "passive"))
      (node (ref "SV4") (pin "5") (pinfunction "5_5") (pintype "passive"))
      (node (ref "SV5") (pin "1") (pinfunction "1_1") (pintype "passive"))
      (node (ref "SV6") (pin "1") (pinfunction "1_1") (pintype "passive"))
      (node (ref "SV7") (pin "2") (pinfunction "2_2") (pintype "passive"))
      (node (ref "SV8") (pin "1") (pinfunction "1_1") (pintype "passive"))
      (node (ref "SV8") (pin "2") (pinfunction "2_2") (pintype "passive"))
      (node (ref "SV9") (pin "1") (pinfunction "1_1") (pintype "passive"))
      (node (ref "SV9") (pin "2") (pinfunction "2_2") (pintype "passive"))
      (node (ref "SWD") (pin "3") (pinfunction "3_3") (pintype "passive"))
      (node (ref "U1") (pin "23") (pinfunction "VSS_23") (pintype "power_in"))
      (node (ref "U1") (pin "35") (pinfunction "VSS_35") (pintype "power_in"))
      (node (ref "U1") (pin "47") (pinfunction "VSS_47") (pintype "power_in"))
      (node (ref "U1") (pin "8") (pinfunction "VSSA_8") (pintype "power_in"))
      (node (ref "U2") (pin "1") (pinfunction "GND_1") (pintype "input"))
      (node (ref "U3") (pin "15") (pinfunction "CONFIG_15") (pintype "passive"))
      (node (ref "U3") (pin "21") (pinfunction "GND_21") (pintype "power_in"))
      (node (ref "U4") (pin "4") (pinfunction "V-_4") (pintype "power_in"))
      (node (ref "U5") (pin "4") (pinfunction "G2A_4") (pintype "input"))
      (node (ref "U5") (pin "5") (pinfunction "G2B_5") (pintype "input"))
      (node (ref "U5") (pin "8") (pinfunction "GND_8") (pintype "power_in"))
      (node (ref "USB") (pin "4") (pinfunction "4_4") (pintype "passive"))
      (node (ref "USB") (pin "S1") (pinfunction "S1_S1") (pintype "passive"))
      (node (ref "USB") (pin "S2") (pinfunction "S2_S2") (pintype "passive"))
      (node (ref "V+") (pin "1") (pinfunction "S_1") (pintype "passive"))
      (node (ref "WIFI") (pin "2") (pinfunction "2_2") (pintype "passive"))
    )
    (net (code "27") (name "I2C2_SCL") (class "Default")
      (node (ref "GY521") (pin "3") (pinfunction "SCL_3") (pintype "input"))
      (node (ref "R13") (pin "1") (pinfunction "1_1") (pintype "passive"))
      (node (ref "SV4") (pin "9") (pinfunction "9_9") (pintype "passive"))
      (node (ref "U1") (pin "21") (pinfunction "PB10/I2C2_SCL/USART3_TX_21") (pintype "bidirectional"))
    )
    (net (code "28") (name "I2C2_SDA") (class "Default")
      (node (ref "GY521") (pin "4") (pinfunction "SDA_4") (pintype "bidirectional"))
      (node (ref "R14") (pin "1") (pinfunction "1_1") (pintype "passive"))
      (node (ref "SV4") (pin "10") (pinfunction "10_10") (pintype "passive"))
      (node (ref "SV4") (pin "12") (pinfunction "12_12") (pintype "passive"))
      (node (ref "U1") (pin "22") (pinfunction "PB11/I2C2_SDA/USART3_RX_22") (pintype "bidirectional"))
    )
    (net (code "29") (name "Net-(C14-Pad1)") (class "Default")
      (node (ref "C14") (pin "1") (pinfunction "1_1") (pintype "passive"))
      (node (ref "C15") (pin "2") (pinfunction "2_2") (pintype "passive"))
      (node (ref "C17") (pin "+") (pinfunction "+_+") (pintype "passive"))
      (node (ref "R24") (pin "1") (pinfunction "1_1") (pintype "passive"))
      (node (ref "U3") (pin "18") (pinfunction "VM_18") (pintype "power_in"))
      (node (ref "U3") (pin "19") (pinfunction "VM_19") (pintype "power_in"))
    )
    (net (code "30") (name "Net-(D1-PadA)") (class "Default")
      (node (ref "D1") (pin "A") (pinfunction "A_A") (pintype "passive"))
      (node (ref "USB") (pin "1") (pinfunction "1_1") (pintype "passive"))
    )
    (net (code "31") (name "Net-(GY521-INT)") (class "Default")
      (node (ref "GY521") (pin "8") (pinfunction "INT_8") (pintype "output"))
      (node (ref "R11") (pin "2") (pinfunction "2_2") (pintype "passive"))
    )
    (net (code "32") (name "Net-(J3-Pad1)") (class "Default")
      (node (ref "J3") (pin "1") (pinfunction "1_1") (pintype "passive"))
      (node (ref "SV12") (pin "4") (pinfunction "4_4") (pintype "passive"))
    )
    (net (code "33") (name "Net-(LCD-Pad1)") (class "Default")
      (node (ref "LCD") (pin "1") (pinfunction "1_1") (pintype "passive"))
      (node (ref "R12") (pin "2") (pinfunction "2_2") (pintype "passive"))
    )
    (net (code "34") (name "Net-(MOTORA-K)") (class "Default")
      (node (ref "MOTOR") (pin "1") (pinfunction "K_1") (pintype "passive"))
      (node (ref "U3") (pin "4") (pinfunction "AOUT1_4") (pintype "passive"))
    )
    (net (code "35") (name "Net-(MOTORB-K)") (class "Default")
      (node (ref "MOTOR") (pin "2") (pinfunction "K_2") (pintype "passive"))
      (node (ref "U3") (pin "6") (pinfunction "AOUT2_6") (pintype "passive"))
    )
    (net (code "36") (name "Net-(MOTORC-K)") (class "Default")
      (node (ref "MOTOR") (pin "3") (pinfunction "K_3") (pintype "passive"))
      (node (ref "U3") (pin "7") (pinfunction "BOUT2_7") (pintype "passive"))
    )
    (net (code "37") (name "Net-(MOTORD-K)") (class "Default")
      (node (ref "MOTOR") (pin "4") (pinfunction "K_4") (pintype "passive"))
      (node (ref "U3") (pin "9") (pinfunction "BOUT1_9") (pintype "passive"))
    )
    (net (code "38") (name "Net-(OK1-C)") (class "Default")
      (node (ref "OK1") (pin "2") (pinfunction "C_2") (pintype "passive"))
      (node (ref "OK3") (pin "2") (pinfunction "C_2") (pintype "passive"))
      (node (ref "R25") (pin "1") (pinfunction "1_1") (pintype "passive"))
    )
    (net (code "39") (name "Net-(OK1-EMIT)") (class "Default")
      (node (ref "OK1") (pin "4") (pinfunction "EMIT_4") (pintype "passive"))
      (node (ref "OK3") (pin "4") (pinfunction "EMIT_4") (pintype "passive"))
      (node (ref "R20") (pin "1") (pinfunction "1_1") (pintype "passive"))
      (node (ref "R26") (pin "2") (pinfunction "2_2") (pintype "passive"))
      (node (ref "SV5") (pin "3") (pinfunction "3_3") (pintype "passive"))
      (node (ref "SV6") (pin "4") (pinfunction "4_4") (pintype "passive"))
      (node (ref "SV7") (pin "3") (pinfunction "3_3") (pintype "passive"))
    )
    (net (code "40") (name "Net-(OK2-A)") (class "Default")
      (node (ref "OK2") (pin "1") (pinfunction "A_1") (pintype "passive"))
      (node (ref "OK4") (pin "1") (pinfunction "A_1") (pintype "passive"))
      (node (ref "R25") (pin "2") (pinfunction "2_2") (pintype "passive"))
    )
    (net (code "41") (name "Net-(OK2-EMIT)") (class "Default")
      (node (ref "OK2") (pin "4") (pinfunction "EMIT_4") (pintype "passive"))
      (node (ref "OK4") (pin "4") (pinfunction "EMIT_4") (pintype "passive"))
      (node (ref "R16") (pin "1") (pinfunction "1_1") (pintype "passive"))
      (node (ref "R27") (pin "2") (pinfunction "2_2") (pintype "passive"))
      (node (ref "SV6") (pin "3") (pinfunction "3_3") (pintype "passive"))
      (node (ref "SV7") (pin "4") (pinfunction "4_4") (pintype "passive"))
    )
    (net (code "42") (name "Net-(R4-Pad2)") (class "Default")
      (node (ref "R4") (pin "2") (pinfunction "2_2") (pintype "passive"))
      (node (ref "RA0") (pin "A") (pinfunction "A_A") (pintype "passive"))
    )
    (net (code "43") (name "Net-(R18-Pad1)") (class "Default")
      (node (ref "R18") (pin "1") (pinfunction "1_1") (pintype "passive"))
      (node (ref "R19") (pin "1") (pinfunction "1_1") (pintype "passive"))
      (node (ref "R30") (pin "2") (pinfunction "2_2") (pintype "passive"))
    )
    (net (code "44") (name "Net-(R22-Pad1)") (class "Default")
      (node (ref "R22") (pin "1") (pinfunction "1_1") (pintype "passive"))
      (node (ref "R23") (pin "1") (pinfunction "1_1") (pintype "passive"))
      (node (ref "R31") (pin "2") (pinfunction "2_2") (pintype "passive"))
    )
    (net (code "45") (name "Net-(R35-Pad1)") (class "Default")
      (node (ref "R35") (pin "1") (pinfunction "1_1") (pintype "passive"))
      (node (ref "SV12") (pin "2") (pinfunction "2_2") (pintype "passive"))
    )
    (net (code "46") (name "Net-(RESET-P1)") (class "Default")
      (node (ref "R3") (pin "1") (pinfunction "1_1") (pintype "passive"))
      (node (ref "RESET") (pin "4") (pinfunction "P1_4") (pintype "passive"))
    )
    (net (code "47") (name "Net-(S1-S)") (class "Default")
      (node (ref "R2") (pin "2") (pinfunction "2_2") (pintype "passive"))
      (node (ref "R5") (pin "1") (pinfunction "1_1") (pintype "passive"))
      (node (ref "S1") (pin "1") (pinfunction "S_1") (pintype "passive"))
    )
    (net (code "48") (name "Net-(S1-S1)") (class "Default")
      (node (ref "C10") (pin "1") (pinfunction "1_1") (pintype "passive"))
      (node (ref "S1") (pin "2") (pinfunction "S1_2") (pintype "passive"))
    )
    (net (code "49") (name "Net-(U1-NRST)") (class "Default")
      (node (ref "R3") (pin "2") (pinfunction "2_2") (pintype "passive"))
      (node (ref "U1") (pin "7") (pinfunction "NRST_7") (pintype "input"))
    )
    (net (code "50") (name "Net-(U1-PA7{slash}SPI1_MOSI{slash}ADC12_IN7{slash}TIM3_CH2)") (class "Default")
      (node (ref "R7") (pin "2") (pinfunction "2_2") (pintype "passive"))
      (node (ref "U1") (pin "17") (pinfunction "PA7/SPI1_MOSI/ADC12_IN7/TIM3_CH2_17") (pintype "bidirectional"))
    )
    (net (code "51") (name "Net-(U2-IN)") (class "Default")
      (node (ref "C13") (pin "+") (pinfunction "+_+") (pintype "passive"))
      (node (ref "D1") (pin "C") (pinfunction "C_C") (pintype "passive"))
      (node (ref "D2") (pin "C") (pinfunction "C_C") (pintype "passive"))
      (node (ref "U2") (pin "3") (pinfunction "IN_3") (pintype "input"))
    )
    (net (code "52") (name "Net-(U3A-ADECAY)") (class "Default")
      (node (ref "R15") (pin "2") (pinfunction "2_2") (pintype "passive"))
      (node (ref "U3") (pin "3") (pinfunction "ADECAY_3") (pintype "passive"))
    )
    (net (code "53") (name "Net-(U3A-AISEN)") (class "Default")
      (node (ref "R8") (pin "2") (pinfunction "2_2") (pintype "passive"))
      (node (ref "U3") (pin "5") (pinfunction "AISEN_5") (pintype "passive"))
    )
    (net (code "54") (name "Net-(U3A-AVREF)") (class "Default")
      (node (ref "U3") (pin "22") (pinfunction "AVREF_22") (pintype "passive"))
      (node (ref "U3") (pin "23") (pinfunction "BVREF_23") (pintype "passive"))
      (node (ref "U3") (pin "24") (pinfunction "VREFO_24") (pintype "passive"))
    )
    (net (code "55") (name "Net-(U3A-BDECAY)") (class "Default")
      (node (ref "R10") (pin "2") (pinfunction "2_2") (pintype "passive"))
      (node (ref "U3") (pin "2") (pinfunction "BDECAY_2") (pintype "passive"))
    )
    (net (code "56") (name "Net-(U3A-BISEN)") (class "Default")
      (node (ref "R9") (pin "2") (pinfunction "2_2") (pintype "passive"))
      (node (ref "U3") (pin "8") (pinfunction "BISEN_8") (pintype "passive"))
    )
    (net (code "57") (name "Net-(U3A-VCP)") (class "Default")
      (node (ref "C15") (pin "1") (pinfunction "1_1") (pintype "passive"))
      (node (ref "U3") (pin "17") (pinfunction "VCP_17") (pintype "passive"))
    )
    (net (code "58") (name "Net-(U3A-VINT)") (class "Default")
      (node (ref "C16") (pin "1") (pinfunction "1_1") (pintype "passive"))
      (node (ref "U3") (pin "20") (pinfunction "VINT_20") (pintype "passive"))
    )
    (net (code "59") (name "Net-(U4A-+IN)") (class "Default")
      (node (ref "R21") (pin "2") (pinfunction "2_2") (pintype "passive"))
      (node (ref "R31") (pin "1") (pinfunction "1_1") (pintype "passive"))
      (node (ref "U4") (pin "3") (pinfunction "+IN_3") (pintype "input"))
    )
    (net (code "60") (name "Net-(U4A--IN)") (class "Default")
      (node (ref "C20") (pin "1") (pinfunction "1_1") (pintype "passive"))
      (node (ref "R16") (pin "2") (pinfunction "2_2") (pintype "passive"))
      (node (ref "U4") (pin "2") (pinfunction "-IN_2") (pintype "input"))
    )
    (net (code "61") (name "Net-(U4B-+IN)") (class "Default")
      (node (ref "R17") (pin "2") (pinfunction "2_2") (pintype "passive"))
      (node (ref "R30") (pin "1") (pinfunction "1_1") (pintype "passive"))
      (node (ref "U4") (pin "5") (pinfunction "+IN_5") (pintype "input"))
    )
    (net (code "62") (name "Net-(U4B--IN)") (class "Default")
      (node (ref "C19") (pin "1") (pinfunction "1_1") (pintype "passive"))
      (node (ref "R20") (pin "2") (pinfunction "2_2") (pintype "passive"))
      (node (ref "U4") (pin "6") (pinfunction "-IN_6") (pintype "input"))
    )
    (net (code "63") (name "Net-(U4B-OUT)") (class "Default")
      (node (ref "J2") (pin "1") (pinfunction "1_1") (pintype "passive"))
      (node (ref "R18") (pin "2") (pinfunction "2_2") (pintype "passive"))
      (node (ref "U4") (pin "7") (pinfunction "OUT_7") (pintype "output"))
    )
    (net (code "64") (name "Net-(U5A-A)") (class "Default")
      (node (ref "R34") (pin "1") (pinfunction "1_1") (pintype "passive"))
      (node (ref "TO_LCD") (pin "1") (pinfunction "1_1") (pintype "passive"))
      (node (ref "U5") (pin "1") (pinfunction "A_1") (pintype "input"))
    )
    (net (code "65") (name "Net-(U5A-C)") (class "Default")
      (node (ref "R32") (pin "2") (pinfunction "2_2") (pintype "passive"))
      (node (ref "TO_LCD") (pin "6") (pinfunction "6_6") (pintype "passive"))
      (node (ref "U5") (pin "3") (pinfunction "C_3") (pintype "input"))
    )
    (net (code "66") (name "Net-(U5A-Y0)") (class "Default")
      (node (ref "SV8") (pin "6") (pinfunction "6_6") (pintype "passive"))
      (node (ref "U5") (pin "15") (pinfunction "Y0_15") (pintype "output"))
    )
    (net (code "67") (name "Net-(U5A-Y1)") (class "Default")
      (node (ref "SV9") (pin "5") (pinfunction "5_5") (pintype "passive"))
      (node (ref "U5") (pin "14") (pinfunction "Y1_14") (pintype "output"))
    )
    (net (code "68") (name "Net-(U5A-Y2)") (class "Default")
      (node (ref "SV9") (pin "6") (pinfunction "6_6") (pintype "passive"))
      (node (ref "U5") (pin "13") (pinfunction "Y2_13") (pintype "output"))
    )
    (net (code "69") (name "Net-(U5A-Y3)") (class "Default")
      (node (ref "SV10") (pin "5") (pinfunction "5_5") (pintype "passive"))
      (node (ref "U5") (pin "12") (pinfunction "Y3_12") (pintype "output"))
    )
    (net (code "70") (name "Net-(U5A-Y4)") (class "Default")
      (node (ref "SV10") (pin "6") (pinfunction "6_6") (pintype "passive"))
      (node (ref "U5") (pin "11") (pinfunction "Y4_11") (pintype "output"))
    )
    (net (code "71") (name "Net-(U5A-Y5)") (class "Default")
      (node (ref "SV11") (pin "5") (pinfunction "5_5") (pintype "passive"))
      (node (ref "U5") (pin "10") (pinfunction "Y5_10") (pintype "output"))
    )
    (net (code "72") (name "Net-(U5A-Y6)") (class "Default")
      (node (ref "SV11") (pin "6") (pinfunction "6_6") (pintype "passive"))
      (node (ref "U5") (pin "9") (pinfunction "Y6_9") (pintype "output"))
    )
    (net (code "73") (name "Net-(U5A-Y7)") (class "Default")
      (node (ref "SV8") (pin "5") (pinfunction "5_5") (pintype "passive"))
      (node (ref "U5") (pin "7") (pinfunction "Y7_7") (pintype "output"))
    )
    (net (code "74") (name "PA0") (class "Default")
      (node (ref "SV3") (pin "10") (pinfunction "10_10") (pintype "passive"))
      (node (ref "U1") (pin "10") (pinfunction "PA0/WKUP/USART2_CTS/ADC12_IN0/TIM2_CH1_ETR_10") (pintype "bidirectional"))
      (node (ref "U3") (pin "12") (pinfunction "DIR/BPHASE_12") (pintype "passive"))
    )
    (net (code "75") (name "PA9") (class "Default")
      (node (ref "R11") (pin "1") (pinfunction "1_1") (pintype "passive"))
      (node (ref "SV1") (pin "8") (pinfunction "8_8") (pintype "passive"))
      (node (ref "U1") (pin "30") (pinfunction "USART1_TX/TIM1_CH2/PA9_30") (pintype "bidirectional"))
    )
    (net (code "76") (name "PC14") (class "Default")
      (node (ref "SV3") (pin "3") (pinfunction "3_3") (pintype "passive"))
      (node (ref "U1") (pin "3") (pinfunction "PC14/OSC32_IN_3") (pintype "bidirectional"))
      (node (ref "U3") (pin "14") (pinfunction "M1_14") (pintype "passive"))
    )
    (net (code "77") (name "PC15") (class "Default")
      (node (ref "SV3") (pin "6") (pinfunction "6_6") (pintype "passive"))
      (node (ref "U1") (pin "4") (pinfunction "PC15/OSC32_OUT_4") (pintype "bidirectional"))
      (node (ref "U3") (pin "13") (pinfunction "M0/APHASE_13") (pintype "passive"))
    )
    (net (code "78") (name "SPI2_MISO") (class "Default")
      (node (ref "R12") (pin "1") (pinfunction "1_1") (pintype "passive"))
      (node (ref "SPI2") (pin "8") (pinfunction "8_8") (pintype "passive"))
      (node (ref "SV1") (pin "9") (pinfunction "9_9") (pintype "passive"))
      (node (ref "U1") (pin "27") (pinfunction "SPI2_MISO/USART3_RTS/TIM1_CH2N/PB14_27") (pintype "bidirectional"))
    )
    (net (code "79") (name "SPI2_MOSI") (class "Default")
      (node (ref "LCD") (pin "4") (pinfunction "4_4") (pintype "passive"))
      (node (ref "SPI2") (pin "6") (pinfunction "6_6") (pintype "passive"))
      (node (ref "SV1") (pin "10") (pinfunction "10_10") (pintype "passive"))
      (node (ref "U1") (pin "28") (pinfunction "SPI2_MOSI/TIM1_CH3N/PB15_28") (pintype "bidirectional"))
    )
    (net (code "80") (name "SPI2_NSS") (class "Default")
      (node (ref "LCD") (pin "7") (pinfunction "7_7") (pintype "passive"))
      (node (ref "SPI2") (pin "10") (pinfunction "10_10") (pintype "passive"))
      (node (ref "SV1") (pin "11") (pinfunction "11_11") (pintype "passive"))
      (node (ref "U1") (pin "25") (pinfunction "SPI2_NSS/I2C2_SMBAI/USART3_CK/TIM1_BKIN/PB12_25") (pintype "bidirectional"))
    )
    (net (code "81") (name "SPI2_SCK") (class "Default")
      (node (ref "LCD") (pin "3") (pinfunction "3_3") (pintype "passive"))
      (node (ref "SPI2") (pin "2") (pinfunction "2_2") (pintype "passive"))
      (node (ref "SV1") (pin "12") (pinfunction "12_12") (pintype "passive"))
      (node (ref "U1") (pin "26") (pinfunction "SPI2_SCK/USART3_CTS/TIM1_CH1N/PB13_26") (pintype "bidirectional"))
    )
    (net (code "82") (name "TIM2_CH2") (class "Default")
      (node (ref "J2") (pin "2") (pinfunction "2_2") (pintype "passive"))
      (node (ref "SV3") (pin "12") (pinfunction "12_12") (pintype "passive"))
      (node (ref "U1") (pin "11") (pinfunction "PA1/USART2_RTS/ADC12_IN1/TIM2_CH2_11") (pintype "bidirectional"))
    )
    (net (code "83") (name "TIM3_CH1") (class "Default")
      (node (ref "SV4") (pin "3") (pinfunction "3_3") (pintype "passive"))
      (node (ref "U1") (pin "16") (pinfunction "PA6/SPI1_MISO/ADC12_IN6/TIM3_CH1_16") (pintype "bidirectional"))
      (node (ref "U3") (pin "10") (pinfunction "NENBL/AENBL_10") (pintype "passive"))
    )
    (net (code "84") (name "TIM3_CH2") (class "Default")
      (node (ref "R7") (pin "1") (pinfunction "1_1") (pintype "passive"))
      (node (ref "SV3") (pin "11") (pinfunction "11_11") (pintype "passive"))
      (node (ref "U3") (pin "11") (pinfunction "STEP/BENBL_11") (pintype "passive"))
    )
    (net (code "85") (name "TIM3_CH3") (class "Default")
      (node (ref "SV4") (pin "4") (pinfunction "4_4") (pintype "passive"))
      (node (ref "U1") (pin "18") (pinfunction "PB0/ADC12_IN8/TIM3_CH3_18") (pintype "bidirectional"))
      (node (ref "U5") (pin "6") (pinfunction "G1_6") (pintype "input"))
    )
    (net (code "86") (name "TIM4_CH4") (class "Default")
      (node (ref "R22") (pin "2") (pinfunction "2_2") (pintype "passive"))
      (node (ref "SV2") (pin "1") (pinfunction "1_1") (pintype "passive"))
      (node (ref "U1") (pin "46") (pinfunction "TIM4_CH4/PB9_46") (pintype "bidirectional"))
      (node (ref "U4") (pin "1") (pinfunction "OUT_1") (pintype "output"))
    )
    (net (code "87") (name "USART2_RX") (class "Default")
      (node (ref "U1") (pin "13") (pinfunction "PA3/USART2_RX/ADC12_IN3/TIM2_CH4_13") (pintype "bidirectional"))
      (node (ref "WIFI") (pin "1") (pinfunction "1_1") (pintype "passive"))
    )
    (net (code "88") (name "USART2_TX") (class "Default")
      (node (ref "U1") (pin "12") (pinfunction "PA2/USART2_TX/ADC12_IN2/TIM2_CH3_12") (pintype "bidirectional"))
      (node (ref "WIFI") (pin "8") (pinfunction "8_8") (pintype "passive"))
    )
    (net (code "89") (name "Vmotor+") (class "Default")
      (node (ref "J1") (pin "3") (pinfunction "S_3") (pintype "passive"))
      (node (ref "R24") (pin "2") (pinfunction "2_2") (pintype "passive"))
    )
    (net (code "90") (name "unconnected-(GY521-XCL-Pad6)") (class "Default")
      (node (ref "GY521") (pin "6") (pinfunction "XCL_6") (pintype "output"))
    )
    (net (code "91") (name "unconnected-(GY521-XDA-Pad5)") (class "Default")
      (node (ref "GY521") (pin "5") (pinfunction "XDA_5") (pintype "bidirectional"))
    )
    (net (code "92") (name "unconnected-(JTAGC-KL-Pad11)") (class "Default")
      (node (ref "JTAG") (pin "11") (pinfunction "KL_11") (pintype "passive"))
    )
    (net (code "93") (name "unconnected-(JTAGI-KL-Pad17)") (class "Default")
      (node (ref "JTAG") (pin "17") (pinfunction "KL_17") (pintype "passive"))
    )
    (net (code "94") (name "unconnected-(JTAGK-KL-Pad19)") (class "Default")
      (node (ref "JTAG") (pin "19") (pinfunction "KL_19") (pintype "passive"))
    )
    (net (code "95") (name "unconnected-(SPI2-Pad1)") (class "Default")
      (node (ref "SPI2") (pin "1") (pinfunction "1_1") (pintype "passive"))
    )
    (net (code "96") (name "unconnected-(SPI2-Pad5)") (class "Default")
      (node (ref "SPI2") (pin "5") (pinfunction "5_5") (pintype "passive"))
    )
    (net (code "97") (name "unconnected-(SPI2-Pad7)") (class "Default")
      (node (ref "SPI2") (pin "7") (pinfunction "7_7") (pintype "passive"))
    )
    (net (code "98") (name "unconnected-(SPI2-Pad9)") (class "Default")
      (node (ref "SPI2") (pin "9") (pinfunction "9_9") (pintype "passive"))
    )
    (net (code "99") (name "unconnected-(SV3-Pad1)") (class "Default")
      (node (ref "SV3") (pin "1") (pinfunction "1_1") (pintype "passive"))
    )
    (net (code "100") (name "unconnected-(SV3-Pad5)") (class "Default")
      (node (ref "SV3") (pin "5") (pinfunction "5_5") (pintype "passive"))
    )
    (net (code "101") (name "unconnected-(SV4-Pad11)") (class "Default")
      (node (ref "SV4") (pin "11") (pinfunction "11_11") (pintype "passive"))
    )
    (net (code "102") (name "unconnected-(SWD-Pad6)") (class "Default")
      (node (ref "SWD") (pin "6") (pinfunction "6_6") (pintype "passive"))
    )
    (net (code "103") (name "unconnected-(TO_LCD-Pad3)") (class "Default")
      (node (ref "TO_LCD") (pin "3") (pinfunction "3_3") (pintype "passive"))
    )
    (net (code "104") (name "unconnected-(TO_LCD-Pad5)") (class "Default")
      (node (ref "TO_LCD") (pin "5") (pinfunction "5_5") (pintype "passive"))
    )
    (net (code "105") (name "unconnected-(U3A-NFAULT-Pad16)") (class "Default")
      (node (ref "U3") (pin "16") (pinfunction "NFAULT_16") (pintype "passive"))
    )
    (net (code "106") (name "unconnected-(WIFI-Pad4)") (class "Default")
      (node (ref "WIFI") (pin "4") (pinfunction "4_4") (pintype "passive"))
    )
    (net (code "107") (name "unconnected-(WIFI-Pad5)") (class "Default")
      (node (ref "WIFI") (pin "5") (pinfunction "5_5") (pintype "passive"))
    )
    (net (code "108") (name "unconnected-(WIFI-Pad6)") (class "Default")
      (node (ref "WIFI") (pin "6") (pinfunction "6_6") (pintype "passive"))
    )
  )
)
